# Pg3_Current_Sensor.net
KiCad netlist of a schematic drawn in Altium Designer
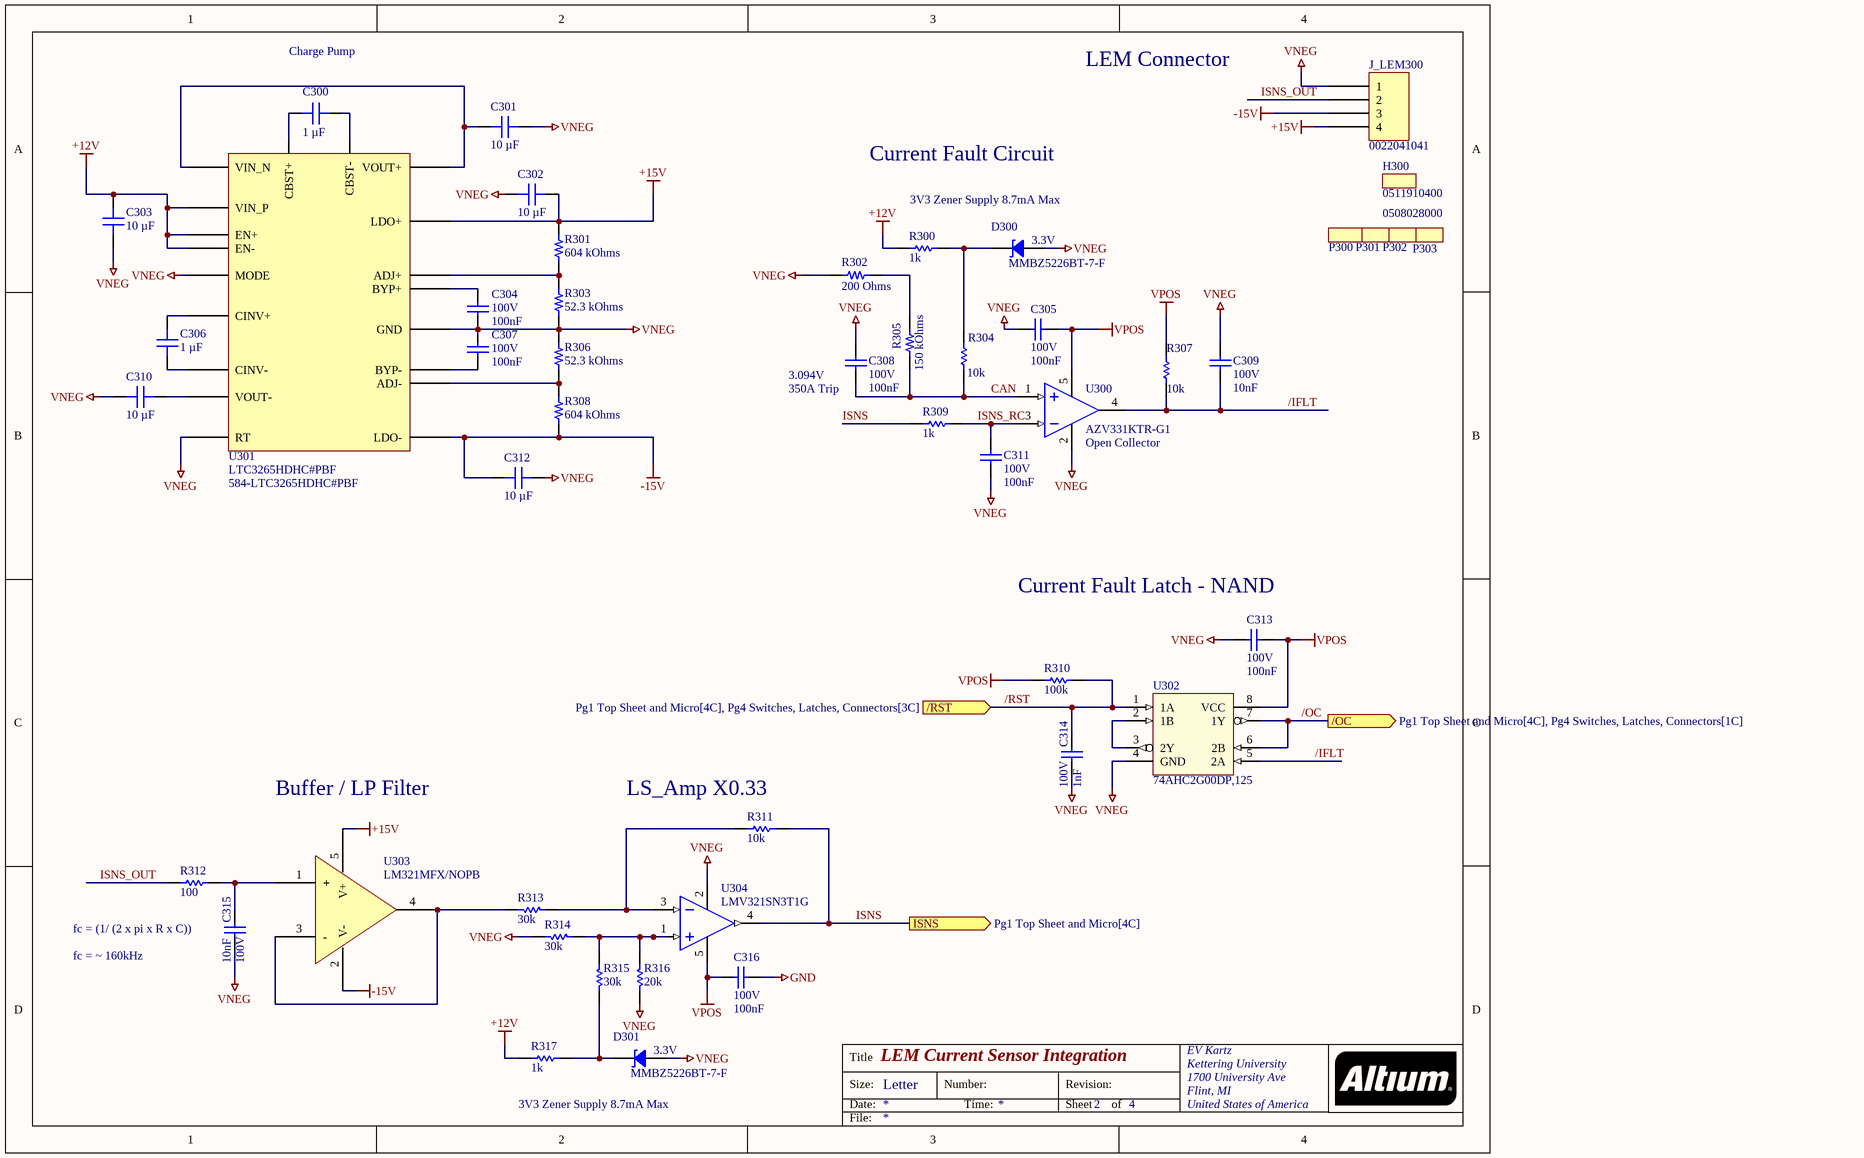
[diagram p0: Pg3 Current Sensor.SchDoc]

(export (version "E")
  (design (tool "Eeschema 10.0.6"))
  (components
    (comp (ref "C300")
      (value "1 µF")
      (footprint "CAP 0805_2012")
      (description "CAP CER 1UF 100V X7S 0805")
      (fields
        (field (name "PART NUMBER") "GRM21BC72A105KE01L")
        (field (name "MANUFACTURER") "Murata Electronics")
      )
      (libsource (lib "Celestial Altium Library - altium_library") (part "Capacitor"))
    )
    (comp (ref "C301")
      (value "10 µF")
      (footprint "CAP 1206_3216 - 0.8MM")
      (description "CAP CER 10UF 25V X5R 1206")
      (fields
        (field (name "PART NUMBER") "1206X106K250CT")
        (field (name "MANUFACTURER") "Walsin Technology Corporation")
      )
      (libsource (lib "Celestial Altium Library - altium_library") (part "Capacitor"))
    )
    (comp (ref "C302")
      (value "10 µF")
      (footprint "CAP 1206_3216 - 0.8MM")
      (description "CAP CER 10UF 25V X5R 1206")
      (fields
        (field (name "PART NUMBER") "1206X106K250CT")
        (field (name "MANUFACTURER") "Walsin Technology Corporation")
      )
      (libsource (lib "Celestial Altium Library - altium_library") (part "Capacitor"))
    )
    (comp (ref "C303")
      (value "10 µF")
      (footprint "CAP 1206_3216 - 0.8MM")
      (description "CAP CER 10UF 25V X5R 1206")
      (fields
        (field (name "PART NUMBER") "1206X106K250CT")
        (field (name "MANUFACTURER") "Walsin Technology Corporation")
      )
      (libsource (lib "Celestial Altium Library - altium_library") (part "Capacitor"))
    )
    (comp (ref "C304")
      (value "100nF")
      (footprint "CAPC2012N")
      (description "Capacitor, Ceramic, 100nF, 100V, 0805, 10%, 125C")
      (fields (field (name "RATED") "100V") (field (name "Comment") "C0805C104K1RACAUTO"))
      (libsource (lib "SchLib - EE391 Master") (part "C0805C104K1RACAUTO"))
    )
    (comp (ref "C305")
      (value "100nF")
      (footprint "CAPC2012N")
      (description "Capacitor, Ceramic, 100nF, 25V, 0805, 10%, 125C")
      (fields (field (name "RATED") "100V") (field (name "Comment") "CL21B104KACNNNC"))
      (libsource (lib "SchLib - EE391 Master") (part "C0805C104K1RACAUTO"))
    )
    (comp (ref "C306")
      (value "1 µF")
      (footprint "CAP 0805_2012")
      (description "CAP CER 1UF 100V X7S 0805")
      (fields
        (field (name "PART NUMBER") "GRM21BC72A105KE01L")
        (field (name "MANUFACTURER") "Murata Electronics")
      )
      (libsource (lib "Celestial Altium Library - altium_library") (part "Capacitor"))
    )
    (comp (ref "C307")
      (value "100nF")
      (footprint "CAPC2012N")
      (description "Capacitor, Ceramic, 100nF, 100V, 0805, 10%, 125C")
      (fields (field (name "RATED") "100V") (field (name "Comment") "C0805C104K1RACAUTO"))
      (libsource (lib "SchLib - EE391 Master") (part "C0805C104K1RACAUTO"))
    )
    (comp (ref "C308")
      (value "100nF")
      (footprint "CAPC2012N")
      (description "Capacitor, Ceramic, 100nF, 25V, 0805, 10%, 125C")
      (fields (field (name "RATED") "100V") (field (name "Comment") "CL21B104KACNNNC"))
      (libsource (lib "SchLib - EE391 Master") (part "C0805C104K1RACAUTO"))
    )
    (comp (ref "C309")
      (value "10nF")
      (footprint "CAPC2012N")
      (description "Capacitor, Ceramic, 10nF, 100V, 0805, 10%, 125C")
      (fields (field (name "RATED") "100V") (field (name "Comment") "C0805C103K1RAC7025"))
      (libsource (lib "SchLib - EE391 Master") (part "C0805C103K1RAC7025"))
    )
    (comp (ref "C310")
      (value "10 µF")
      (footprint "CAP 1206_3216 - 0.8MM")
      (description "CAP CER 10UF 25V X5R 1206")
      (fields
        (field (name "PART NUMBER") "1206X106K250CT")
        (field (name "MANUFACTURER") "Walsin Technology Corporation")
      )
      (libsource (lib "Celestial Altium Library - altium_library") (part "Capacitor"))
    )
    (comp (ref "C311")
      (value "100nF")
      (footprint "CAPC2012N")
      (description "Capacitor, Ceramic, 100nF, 25V, 0805, 10%, 125C")
      (fields (field (name "RATED") "100V") (field (name "Comment") "CL21B104KACNNNC"))
      (libsource (lib "SchLib - EE391 Master") (part "C0805C104K1RACAUTO"))
    )
    (comp (ref "C312")
      (value "10 µF")
      (footprint "CAP 1206_3216 - 0.8MM")
      (description "CAP CER 10UF 25V X5R 1206")
      (fields
        (field (name "PART NUMBER") "1206X106K250CT")
        (field (name "MANUFACTURER") "Walsin Technology Corporation")
      )
      (libsource (lib "Celestial Altium Library - altium_library") (part "Capacitor"))
    )
    (comp (ref "C313")
      (value "100nF")
      (footprint "CAPC2012N")
      (description "Capacitor, Ceramic, 100nF, 25V, 0805, 10%, 125C")
      (fields (field (name "RATED") "100V") (field (name "Comment") "CL21B104KACNNNC"))
      (libsource (lib "SchLib - EE391 Master") (part "C0805C104K1RACAUTO"))
    )
    (comp (ref "C314")
      (value "1nF")
      (footprint "CAPC2012N")
      (description "Capacitor, Ceramic, 1nF, 100V, 0805, 10%, 125C")
      (fields (field (name "RATED") "100V") (field (name "Comment") "C0805C102K1RACAUTO"))
      (libsource (lib "SchLib - EE391 Master") (part "C0805C102K1RACAUTO"))
    )
    (comp (ref "C315")
      (value "10nF")
      (footprint "CAPC2012N")
      (description "Capacitor, Ceramic, 10nF, 100V, 0805, 10%, 125C")
      (fields (field (name "RATED") "100V") (field (name "Comment") "C0805C103K1RAC7025"))
      (libsource (lib "SchLib - EE391 Master") (part "C0805C103K1RAC7025"))
    )
    (comp (ref "C316")
      (value "100nF")
      (footprint "CAPC2012N")
      (description "Capacitor, Ceramic, 100nF, 100V, 0805, 10%, 125C")
      (fields (field (name "RATED") "100V") (field (name "Comment") "C0805C104K1RACAUTO"))
      (libsource (lib "SchLib - EE391 Master") (part "C0805C104K1RACAUTO"))
    )
    (comp (ref "D300")
      (value "MMBZ5226BT-7-F")
      (footprint "DIODES SOT-523")
      (description "DIODE ZENER 3.3V 150MW SOT523")
      (fields (field (name "MANUFACTURER") "Diodes Incorporated") (field (name "TOLERANCE") "±5%"))
      (libsource (lib "Celestial Altium Library - altium_library") (part "Diode Zener"))
    )
    (comp (ref "D301")
      (value "MMBZ5226BT-7-F")
      (footprint "DIODES SOT-523")
      (description "DIODE ZENER 3.3V 150MW SOT523")
      (fields (field (name "MANUFACTURER") "Diodes Incorporated") (field (name "TOLERANCE") "±5%"))
      (libsource (lib "Celestial Altium Library - altium_library") (part "Diode Zener"))
    )
    (comp (ref "H300")
      (value "0511910400")
      (description "Housing, Molex, Maiting Part 0511910400")
      (libsource (lib "Connectors") (part "0022041041(Housing)"))
    )
    (comp (ref "J_LEM300")
      (value "0022041041")
      (footprint "0022041041")
      (description "Header, 4 pos, 2.5mm pitch, Molex\r\nKit Parts\r\nHousing: 0511910400\r\nTerminals: 0508028000")
      (libsource (lib "Connectors") (part "0022041041"))
    )
    (comp (ref "P300")
      (value "0508028000")
      (description "Terminal, Molex, Maiting Part 0511910400")
      (libsource (lib "Connectors") (part "0022041041(Terminal)"))
    )
    (comp (ref "P301")
      (value "0508028000")
      (description "Terminal, Molex, Maiting Part 0511910400")
      (libsource (lib "Connectors") (part "0022041041(Terminal)"))
    )
    (comp (ref "P302")
      (value "0508028000")
      (description "Terminal, Molex, Maiting Part 0511910400")
      (libsource (lib "Connectors") (part "0022041041(Terminal)"))
    )
    (comp (ref "P303")
      (value "0508028000")
      (description "Terminal, Molex, Maiting Part 0511910400")
      (libsource (lib "Connectors") (part "0022041041(Terminal)"))
    )
    (comp (ref "R300")
      (value "1k")
      (footprint "RESC2012N")
      (description "Resistor, Fixed, 1 kOhm, 0805, 1%, 1/8W")
      (fields (field (name "Comment") "ERJ-6ENF1001V"))
      (libsource (lib "SchLib - EE391 Master") (part "ERJ-6ENF1001V"))
    )
    (comp (ref "R301")
      (value "604 kOhms")
      (footprint "RES 0805_2012")
      (description "RES 604K OHM 1% 1/8W 0805")
      (fields
        (field (name "PART NUMBER") "RMCF0805FT604K")
        (field (name "MANUFACTURER") "Stackpole Electronics Inc")
      )
      (libsource (lib "Celestial Altium Library - altium_library") (part "Resistor"))
    )
    (comp (ref "R302")
      (value "200 Ohms")
      (footprint "RES 0805_2012")
      (description "RES 200 OHM 0.5% 1/8W 0805")
      (fields
        (field (name "PART NUMBER") "ERA-6AED201V")
        (field (name "MANUFACTURER") "Panasonic Electronic Components")
      )
      (libsource (lib "Celestial Altium Library - altium_library") (part "Resistor"))
    )
    (comp (ref "R303")
      (value "52.3 kOhms")
      (footprint "RES 0805_2012")
      (description "RES 52.3K OHM 1% 1/8W 0805")
      (fields
        (field (name "PART NUMBER") "RMCF0805FT52K3")
        (field (name "MANUFACTURER") "Stackpole Electronics Inc")
      )
      (libsource (lib "Celestial Altium Library - altium_library") (part "Resistor"))
    )
    (comp (ref "R304")
      (value "10k")
      (footprint "RESC2012N")
      (description "Resistor, Fixed, 10 kOhm, 0805, 1%, 1/8W")
      (fields (field (name "Comment") "ERJ-6ENF1002V"))
      (libsource (lib "SchLib - EE391 Master") (part "ERJ-6ENF1002V"))
    )
    (comp (ref "R305")
      (value "150 kOhms")
      (footprint "RES 0805_2012")
      (description "RES 150K OHM 0.1% 1/8W 0805")
      (fields
        (field (name "PART NUMBER") "ERA-6AEB154V")
        (field (name "MANUFACTURER") "Panasonic Electronic Components")
      )
      (libsource (lib "Celestial Altium Library - altium_library") (part "Resistor"))
    )
    (comp (ref "R306")
      (value "52.3 kOhms")
      (footprint "RES 0805_2012")
      (description "RES 52.3K OHM 1% 1/8W 0805")
      (fields
        (field (name "PART NUMBER") "RMCF0805FT52K3")
        (field (name "MANUFACTURER") "Stackpole Electronics Inc")
      )
      (libsource (lib "Celestial Altium Library - altium_library") (part "Resistor"))
    )
    (comp (ref "R307")
      (value "10k")
      (footprint "RESC2012N")
      (description "Resistor, Fixed, 10 kOhm, 0805, 1%, 1/8W")
      (fields (field (name "Comment") "ERJ-6ENF1002V"))
      (libsource (lib "SchLib - EE391 Master") (part "ERJ-6ENF1002V"))
    )
    (comp (ref "R308")
      (value "604 kOhms")
      (footprint "RES 0805_2012")
      (description "RES 604K OHM 1% 1/8W 0805")
      (fields
        (field (name "PART NUMBER") "RMCF0805FT604K")
        (field (name "MANUFACTURER") "Stackpole Electronics Inc")
      )
      (libsource (lib "Celestial Altium Library - altium_library") (part "Resistor"))
    )
    (comp (ref "R309")
      (value "1k")
      (footprint "RESC2012N")
      (description "Resistor, Fixed, 1 kOhm, 0805, 1%, 1/8W")
      (fields (field (name "Comment") "ERJ-6ENF1001V"))
      (libsource (lib "SchLib - EE391 Master") (part "ERJ-6ENF1001V"))
    )
    (comp (ref "R310")
      (value "100k")
      (footprint "RESC2012N")
      (description "Resistor, Fixed, 100 kOhm, 0805, 1%, 1/8W")
      (fields (field (name "Comment") "ERJ-6ENF1003V"))
      (libsource (lib "SchLib - EE391 Master") (part "ERJ-6ENF1003V"))
    )
    (comp (ref "R311")
      (value "10k")
      (footprint "RESC2012N")
      (description "Resistor, Fixed, 10 kOhm, 0805, 1%, 1/8W")
      (fields (field (name "Comment") "ERJ-6ENF1002V"))
      (libsource (lib "SchLib - EE391 Master") (part "ERJ-6ENF1002V"))
    )
    (comp (ref "R312")
      (value "100")
      (footprint "RESC2012N")
      (description "Resistor, Fixed, 100 Ohm, 0805, 1%, 1/8W")
      (fields (field (name "Comment") "ERJ-6ENF1000V"))
      (libsource (lib "SchLib - EE391 Master") (part "ERJ-6ENF1000V"))
    )
    (comp (ref "R313")
      (value "30k")
      (footprint "RESC2012N")
      (description "Resistor, Fixed, 30 kOhm, 0805, 1%, 1/8W")
      (fields (field (name "Comment") "ERJ-6ENF3002V"))
      (libsource (lib "SchLib - EE391 Master") (part "ERJ-6ENF2002V"))
    )
    (comp (ref "R314")
      (value "30k")
      (footprint "RESC2012N")
      (description "Resistor, Fixed, 30 kOhm, 0805, 1%, 1/8W")
      (fields (field (name "Comment") "ERJ-6ENF3002V"))
      (libsource (lib "SchLib - EE391 Master") (part "ERJ-6ENF2002V"))
    )
    (comp (ref "R315")
      (value "30k")
      (footprint "RESC2012N")
      (description "Resistor, Fixed, 30 kOhm, 0805, 1%, 1/8W")
      (fields (field (name "Comment") "ERJ-6ENF3002V"))
      (libsource (lib "SchLib - EE391 Master") (part "ERJ-6ENF2002V"))
    )
    (comp (ref "R316")
      (value "20k")
      (footprint "RESC2012N")
      (description "Resistor, Fixed, 20 kOhm, 0805, 1%, 1/8W")
      (fields (field (name "Comment") "ERJ-6ENF2002V"))
      (libsource (lib "SchLib - EE391 Master") (part "ERJ-6ENF2002V"))
    )
    (comp (ref "R317")
      (value "1k")
      (footprint "RESC2012N")
      (description "Resistor, Fixed, 1 kOhm, 0805, 1%, 1/8W")
      (fields (field (name "Comment") "ERJ-6ENF1001V"))
      (libsource (lib "SchLib - EE391 Master") (part "ERJ-6ENF1001V"))
    )
    (comp (ref "U300")
      (value "AZV331KTR-G1")
      (footprint "SOT23-5N")
      (description "Comparator, Single, Open-Drain, 84mA, 2.2V~5.5V")
      (libsource (lib "SchLib - EE391 Master") (part "AZV331"))
    )
    (comp (ref "U301")
      (value "LTC3265HDHC#PBF")
      (footprint "DHC")
      (description "Supply, Bipolar Charge Pump, +/-15V")
      (fields (field (name "SUPPLIER PART NUMBER 1") "584-LTC3265HDHC#PBF"))
      (libsource (lib "SchLib - EE391 Master") (part "LTC3265HDHC"))
    )
    (comp (ref "U302")
      (value "74AHC2G00DP,125")
      (footprint "TSSOP-8")
      (description "Logic, NAND, Dual, Schmitt Trigger, TSSOP-8")
      (libsource (lib "SchLib - EE391 Master") (part "74AHC2G00"))
    )
    (comp (ref "U303")
      (value "LM321MFX/NOPB")
      (footprint "TI SOT-23-5 DBV")
      (description "IC OPAMP GP 1 CIRCUIT SOT23-5")
      (fields (field (name "MANUFACTURER") "Texas Instruments"))
      (libsource (lib "Celestial Altium Library - altium_library") (part "TI LM321"))
    )
    (comp (ref "U304")
      (value "LMV321SN3T1G")
      (footprint "SOT23-5N")
      (description "Op-Amp, Single, 1MHz, 1V/us, R2R, 2.7V~5.5V, 160mA")
      (libsource (lib "SchLib - EE391 Master") (part "LMV321"))
    )
  )
  (nets
    (net (code "1") (name "+12V") (class "Default")
      (node (ref "C303") (pin "1") (pinfunction "1_1") (pintype "passive"))
      (node (ref "R300") (pin "1") (pinfunction "1_1") (pintype "passive"))
      (node (ref "R317") (pin "1") (pinfunction "1_1") (pintype "passive"))
      (node (ref "U301") (pin "13") (pinfunction "EN+_13") (pintype "passive"))
      (node (ref "U301") (pin "3") (pinfunction "VIN_P_3") (pintype "passive"))
      (node (ref "U301") (pin "4") (pinfunction "EN-_4") (pintype "passive"))
    )
    (net (code "2") (name "+15V") (class "Default")
      (node (ref "C302") (pin "2") (pinfunction "2_2") (pintype "passive"))
      (node (ref "J_LEM300") (pin "4") (pinfunction "4_4") (pintype "passive"))
      (node (ref "R301") (pin "2") (pinfunction "2_2") (pintype "passive"))
      (node (ref "U301") (pin "17") (pinfunction "LDO+_17") (pintype "passive"))
      (node (ref "U303") (pin "5") (pinfunction "V+_5") (pintype "passive"))
    )
    (net (code "3") (name "-15V") (class "Default")
      (node (ref "C312") (pin "2") (pinfunction "2_2") (pintype "passive"))
      (node (ref "J_LEM300") (pin "3") (pinfunction "3_3") (pintype "passive"))
      (node (ref "R308") (pin "1") (pinfunction "1_1") (pintype "passive"))
      (node (ref "U301") (pin "7") (pinfunction "LDO-_7") (pintype "passive"))
      (node (ref "U303") (pin "2") (pinfunction "V-_2") (pintype "passive"))
    )
    (net (code "4") (name "/CAN") (class "Default")
      (node (ref "C308") (pin "2") (pinfunction "2_2") (pintype "passive"))
      (node (ref "R304") (pin "2") (pinfunction "2_2") (pintype "passive"))
      (node (ref "R305") (pin "1") (pinfunction "1_1") (pintype "passive"))
      (node (ref "U300") (pin "1") (pinfunction "IN+_1") (pintype "input"))
    )
    (net (code "5") (name "/ISNS") (class "Default")
      (node (ref "R309") (pin "1") (pinfunction "1_1") (pintype "passive"))
      (node (ref "R311") (pin "1") (pinfunction "1_1") (pintype "passive"))
      (node (ref "U304") (pin "4") (pinfunction "OUT_4") (pintype "output"))
    )
    (net (code "6") (name "/ISNS_OUT") (class "Default")
      (node (ref "J_LEM300") (pin "2") (pinfunction "2_2") (pintype "passive"))
      (node (ref "R312") (pin "1") (pinfunction "1_1") (pintype "passive"))
    )
    (net (code "7") (name "/ISNS_RC") (class "Default")
      (node (ref "C311") (pin "1") (pinfunction "1_1") (pintype "passive"))
      (node (ref "R309") (pin "2") (pinfunction "2_2") (pintype "passive"))
      (node (ref "U300") (pin "3") (pinfunction "IN-_3") (pintype "input"))
    )
    (net (code "8") (name "/{slash}IFLT") (class "Default")
      (node (ref "C309") (pin "2") (pinfunction "2_2") (pintype "passive"))
      (node (ref "R307") (pin "2") (pinfunction "2_2") (pintype "passive"))
      (node (ref "U300") (pin "4") (pinfunction "OUT_4") (pintype "open_collector"))
      (node (ref "U302") (pin "5") (pinfunction "2A_5") (pintype "input"))
    )
    (net (code "9") (name "/{slash}OC") (class "Default")
      (node (ref "U302") (pin "6") (pinfunction "2B_6") (pintype "input"))
      (node (ref "U302") (pin "7") (pinfunction "1Y_7") (pintype "output"))
    )
    (net (code "10") (name "/{slash}RST") (class "Default")
      (node (ref "C314") (pin "1") (pinfunction "1_1") (pintype "passive"))
      (node (ref "R310") (pin "1") (pinfunction "1_1") (pintype "passive"))
      (node (ref "U302") (pin "1") (pinfunction "1A_1") (pintype "input"))
    )
    (net (code "11") (name "GND") (class "Default")
      (node (ref "C316") (pin "2") (pinfunction "2_2") (pintype "passive"))
    )
    (net (code "12") (name "Net-(D300-Pad2)") (class "Default")
      (node (ref "D300") (pin "2") (pinfunction "2_2") (pintype "passive"))
      (node (ref "R300") (pin "2") (pinfunction "2_2") (pintype "passive"))
      (node (ref "R304") (pin "1") (pinfunction "1_1") (pintype "passive"))
    )
    (net (code "13") (name "Net-(D301-Pad2)") (class "Default")
      (node (ref "D301") (pin "2") (pinfunction "2_2") (pintype "passive"))
      (node (ref "R315") (pin "1") (pinfunction "1_1") (pintype "passive"))
      (node (ref "R317") (pin "2") (pinfunction "2_2") (pintype "passive"))
    )
    (net (code "14") (name "Net-(R302-Pad2)") (class "Default")
      (node (ref "R302") (pin "2") (pinfunction "2_2") (pintype "passive"))
      (node (ref "R305") (pin "2") (pinfunction "2_2") (pintype "passive"))
    )
    (net (code "15") (name "Net-(U301-ADJ+)") (class "Default")
      (node (ref "R301") (pin "1") (pinfunction "1_1") (pintype "passive"))
      (node (ref "R303") (pin "2") (pinfunction "2_2") (pintype "passive"))
      (node (ref "U301") (pin "16") (pinfunction "ADJ+_16") (pintype "passive"))
    )
    (net (code "16") (name "Net-(U301-ADJ-)") (class "Default")
      (node (ref "R306") (pin "1") (pinfunction "1_1") (pintype "passive"))
      (node (ref "R308") (pin "2") (pinfunction "2_2") (pintype "passive"))
      (node (ref "U301") (pin "6") (pinfunction "ADJ-_6") (pintype "passive"))
    )
    (net (code "17") (name "Net-(U301-BYP+)") (class "Default")
      (node (ref "C304") (pin "1") (pinfunction "1_1") (pintype "passive"))
      (node (ref "U301") (pin "15") (pinfunction "BYP+_15") (pintype "passive"))
    )
    (net (code "18") (name "Net-(U301-BYP-)") (class "Default")
      (node (ref "C307") (pin "2") (pinfunction "2_2") (pintype "passive"))
      (node (ref "U301") (pin "5") (pinfunction "BYP-_5") (pintype "passive"))
    )
    (net (code "19") (name "Net-(U301-CBST+)") (class "Default")
      (node (ref "C300") (pin "1") (pinfunction "1_1") (pintype "passive"))
      (node (ref "U301") (pin "2") (pinfunction "CBST+_2") (pintype "passive"))
    )
    (net (code "20") (name "Net-(U301-CBST-)") (class "Default")
      (node (ref "C300") (pin "2") (pinfunction "2_2") (pintype "passive"))
      (node (ref "U301") (pin "1") (pinfunction "CBST-_1") (pintype "passive"))
    )
    (net (code "21") (name "Net-(U301-CINV+)") (class "Default")
      (node (ref "C306") (pin "2") (pinfunction "2_2") (pintype "passive"))
      (node (ref "U301") (pin "10") (pinfunction "CINV+_10") (pintype "passive"))
    )
    (net (code "22") (name "Net-(U301-CINV-)") (class "Default")
      (node (ref "C306") (pin "1") (pinfunction "1_1") (pintype "passive"))
      (node (ref "U301") (pin "9") (pinfunction "CINV-_9") (pintype "passive"))
    )
    (net (code "23") (name "Net-(U301-VIN_N)") (class "Default")
      (node (ref "C301") (pin "1") (pinfunction "1_1") (pintype "passive"))
      (node (ref "U301") (pin "11") (pinfunction "VIN_N_11") (pintype "passive"))
      (node (ref "U301") (pin "18") (pinfunction "VOUT+_18") (pintype "passive"))
    )
    (net (code "24") (name "Net-(U301-VOUT-)") (class "Default")
      (node (ref "C310") (pin "1") (pinfunction "1_1") (pintype "passive"))
      (node (ref "U301") (pin "8") (pinfunction "VOUT-_8") (pintype "passive"))
    )
    (net (code "25") (name "Net-(U302-1B)") (class "Default")
      (node (ref "U302") (pin "2") (pinfunction "1B_2") (pintype "input"))
      (node (ref "U302") (pin "3") (pinfunction "2Y_3") (pintype "output"))
    )
    (net (code "26") (name "Net-(U303-+)") (class "Default")
      (node (ref "C315") (pin "1") (pinfunction "1_1") (pintype "passive"))
      (node (ref "R312") (pin "2") (pinfunction "2_2") (pintype "passive"))
      (node (ref "U303") (pin "1") (pinfunction "+_1") (pintype "passive"))
    )
    (net (code "27") (name "Net-(U303--)") (class "Default")
      (node (ref "R313") (pin "2") (pinfunction "2_2") (pintype "passive"))
      (node (ref "U303") (pin "3") (pinfunction "-_3") (pintype "passive"))
      (node (ref "U303") (pin "4") (pinfunction "OUT_4") (pintype "passive"))
    )
    (net (code "28") (name "Net-(U304-IN+)") (class "Default")
      (node (ref "R314") (pin "1") (pinfunction "1_1") (pintype "passive"))
      (node (ref "R315") (pin "2") (pinfunction "2_2") (pintype "passive"))
      (node (ref "R316") (pin "2") (pinfunction "2_2") (pintype "passive"))
      (node (ref "U304") (pin "1") (pinfunction "IN+_1") (pintype "input"))
    )
    (net (code "29") (name "Net-(U304-IN-)") (class "Default")
      (node (ref "R311") (pin "2") (pinfunction "2_2") (pintype "passive"))
      (node (ref "R313") (pin "1") (pinfunction "1_1") (pintype "passive"))
      (node (ref "U304") (pin "3") (pinfunction "IN-_3") (pintype "input"))
    )
    (net (code "30") (name "VNEG") (class "Default")
      (node (ref "C301") (pin "2") (pinfunction "2_2") (pintype "passive"))
      (node (ref "C302") (pin "1") (pinfunction "1_1") (pintype "passive"))
      (node (ref "C303") (pin "2") (pinfunction "2_2") (pintype "passive"))
      (node (ref "C304") (pin "2") (pinfunction "2_2") (pintype "passive"))
      (node (ref "C305") (pin "2") (pinfunction "2_2") (pintype "passive"))
      (node (ref "C307") (pin "1") (pinfunction "1_1") (pintype "passive"))
      (node (ref "C308") (pin "1") (pinfunction "1_1") (pintype "passive"))
      (node (ref "C309") (pin "1") (pinfunction "1_1") (pintype "passive"))
      (node (ref "C310") (pin "2") (pinfunction "2_2") (pintype "passive"))
      (node (ref "C311") (pin "2") (pinfunction "2_2") (pintype "passive"))
      (node (ref "C312") (pin "1") (pinfunction "1_1") (pintype "passive"))
      (node (ref "C313") (pin "2") (pinfunction "2_2") (pintype "passive"))
      (node (ref "C314") (pin "2") (pinfunction "2_2") (pintype "passive"))
      (node (ref "C315") (pin "2") (pinfunction "2_2") (pintype "passive"))
      (node (ref "D300") (pin "1") (pinfunction "1_1") (pintype "passive"))
      (node (ref "D301") (pin "1") (pinfunction "1_1") (pintype "passive"))
      (node (ref "J_LEM300") (pin "1") (pinfunction "1_1") (pintype "passive"))
      (node (ref "R302") (pin "1") (pinfunction "1_1") (pintype "passive"))
      (node (ref "R303") (pin "1") (pinfunction "1_1") (pintype "passive"))
      (node (ref "R306") (pin "2") (pinfunction "2_2") (pintype "passive"))
      (node (ref "R314") (pin "2") (pinfunction "2_2") (pintype "passive"))
      (node (ref "R316") (pin "1") (pinfunction "1_1") (pintype "passive"))
      (node (ref "U300") (pin "2") (pinfunction "VEE_2") (pintype "power_in"))
      (node (ref "U301") (pin "12") (pinfunction "RT_12") (pintype "passive"))
      (node (ref "U301") (pin "14") (pinfunction "MODE_14") (pintype "passive"))
      (node (ref "U301") (pin "19") (pinfunction "GND_19") (pintype "passive"))
      (node (ref "U302") (pin "4") (pinfunction "GND_4") (pintype "power_in"))
      (node (ref "U304") (pin "2") (pinfunction "V-_2") (pintype "power_in"))
    )
    (net (code "31") (name "VPOS") (class "Default")
      (node (ref "C305") (pin "1") (pinfunction "1_1") (pintype "passive"))
      (node (ref "C313") (pin "1") (pinfunction "1_1") (pintype "passive"))
      (node (ref "C316") (pin "1") (pinfunction "1_1") (pintype "passive"))
      (node (ref "R307") (pin "1") (pinfunction "1_1") (pintype "passive"))
      (node (ref "R310") (pin "2") (pinfunction "2_2") (pintype "passive"))
      (node (ref "U300") (pin "5") (pinfunction "VCC_5") (pintype "power_in"))
      (node (ref "U302") (pin "8") (pinfunction "VCC_8") (pintype "power_in"))
      (node (ref "U304") (pin "5") (pinfunction "V+_5") (pintype "power_in"))
    )
  )
)
